# SCH_carw_2026-01-21.net
KiCad netlist of a schematic drawn in EasyEDA
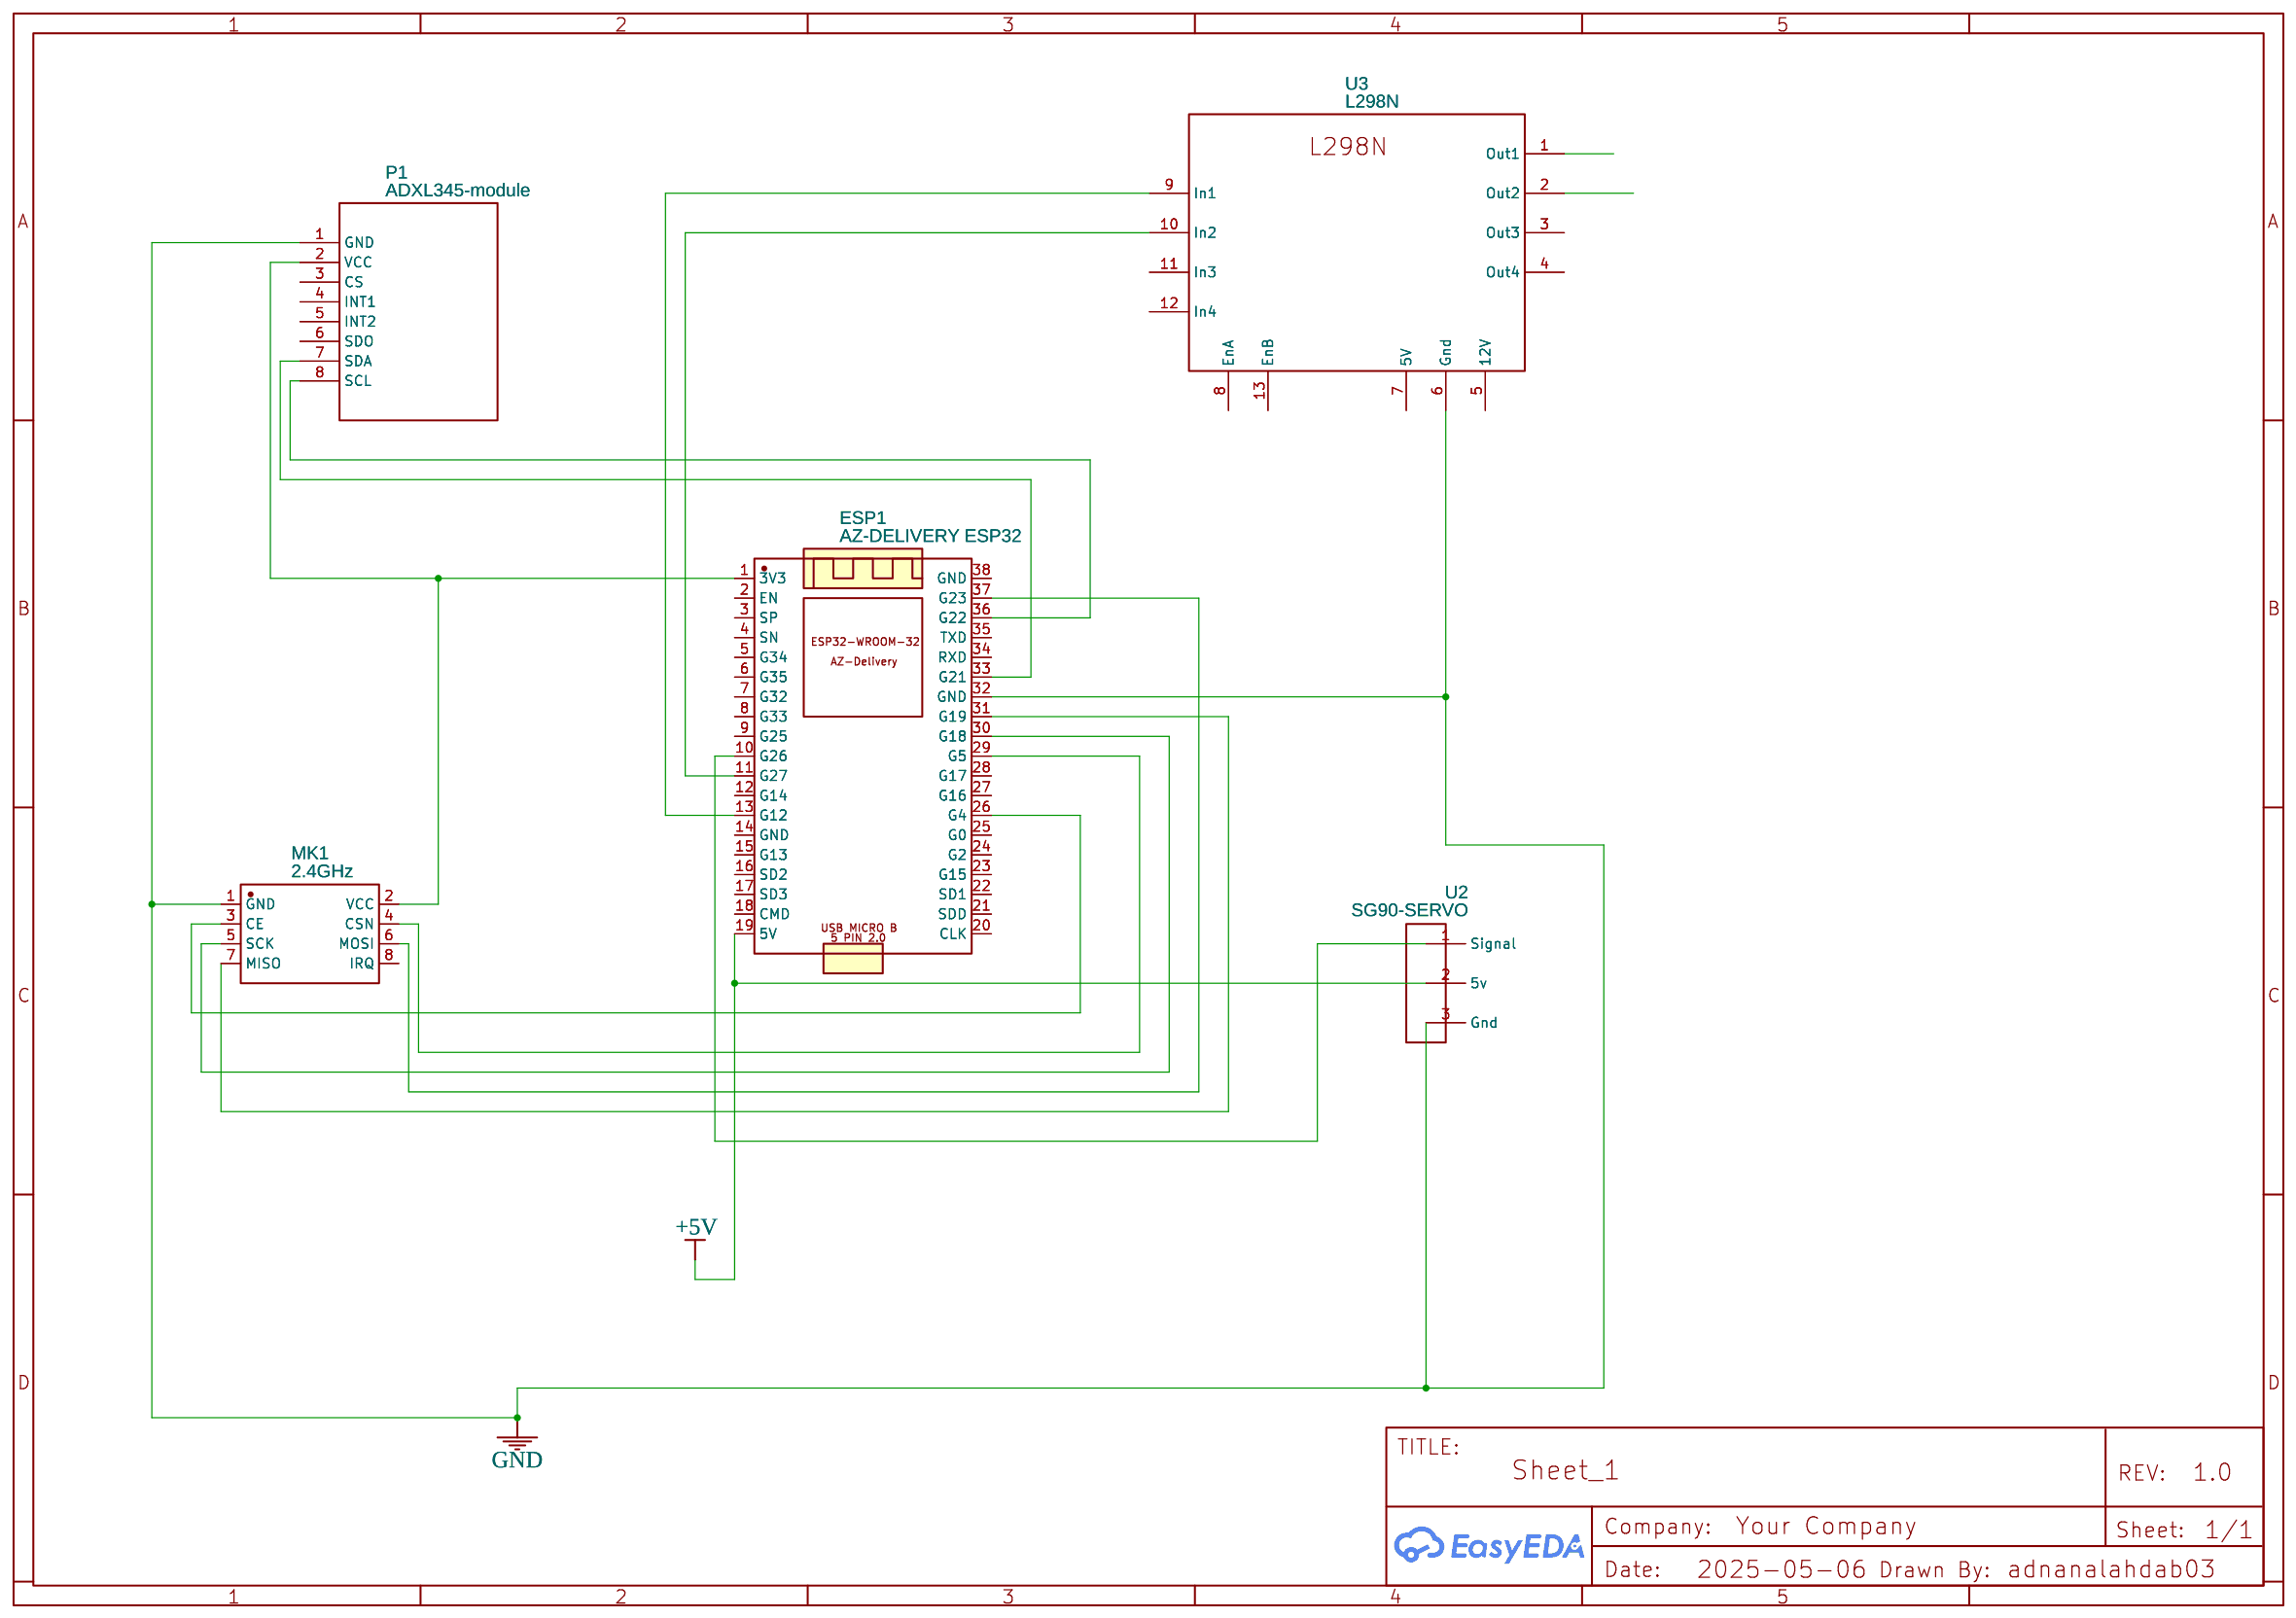
[diagram p0: schematic sheet]

(export (version "E")
  (design (tool "Eeschema 10.0.6"))
  (components
    (comp (ref "ESP1")
      (value "AZ-DELIVERY ESP32")
      (fields (field (name "Manufacturer") "AZ-DELIVERY"))
      (libsource (lib "") (part "AZ-DELIVERY ESP32"))
    )
    (comp (ref "MK1")
      (value "2.4GHz")
      (fields (field (name "Manufacturer Part") "NF-04") (field (name "Manufacturer") "Ai-Thinker(安信可)"))
      (libsource (lib "") (part "NRF24L01"))
    )
    (comp (ref "P1") (value "ADXL345-module") (libsource (lib "") (part "ADXL345-module")))
    (comp (ref "U2") (value "SG90-SERVO") (libsource (lib "") (part "SG90-SERVO")))
    (comp (ref "U3") (value "L298N") (libsource (lib "") (part "L298N")))
  )
  (nets
    (net (code "1") (name "+5V") (class "Default")
      (node (ref "ESP1") (pin "19") (pinfunction "5V_19") (pintype "passive"))
      (node (ref "U2") (pin "2") (pinfunction "5v_2") (pintype "unspecified"))
    )
    (net (code "2") (name "GND") (class "Default")
      (node (ref "ESP1") (pin "32") (pinfunction "GND_32") (pintype "unspecified"))
      (node (ref "MK1") (pin "1") (pinfunction "GND_1") (pintype "unspecified"))
      (node (ref "P1") (pin "1") (pinfunction "GND_1") (pintype "unspecified"))
      (node (ref "U2") (pin "3") (pinfunction "Gnd_3") (pintype "unspecified"))
      (node (ref "U3") (pin "6") (pinfunction "Gnd_6") (pintype "unspecified"))
    )
    (net (code "3") (name "Net-(ESP1-3V3)") (class "Default")
      (node (ref "ESP1") (pin "1") (pinfunction "3V3_1") (pintype "passive"))
      (node (ref "MK1") (pin "2") (pinfunction "VCC_2") (pintype "unspecified"))
      (node (ref "P1") (pin "2") (pinfunction "VCC_2") (pintype "unspecified"))
    )
    (net (code "4") (name "Net-(ESP1-G4)") (class "Default")
      (node (ref "ESP1") (pin "26") (pinfunction "G4_26") (pintype "unspecified"))
      (node (ref "MK1") (pin "3") (pinfunction "CE_3") (pintype "unspecified"))
    )
    (net (code "5") (name "Net-(ESP1-G5)") (class "Default")
      (node (ref "ESP1") (pin "29") (pinfunction "G5_29") (pintype "unspecified"))
      (node (ref "MK1") (pin "4") (pinfunction "CSN_4") (pintype "unspecified"))
    )
    (net (code "6") (name "Net-(ESP1-G12)") (class "Default")
      (node (ref "ESP1") (pin "13") (pinfunction "G12_13") (pintype "unspecified"))
      (node (ref "U3") (pin "9") (pinfunction "In1_9") (pintype "unspecified"))
    )
    (net (code "7") (name "Net-(ESP1-G18)") (class "Default")
      (node (ref "ESP1") (pin "30") (pinfunction "G18_30") (pintype "unspecified"))
      (node (ref "MK1") (pin "5") (pinfunction "SCK_5") (pintype "unspecified"))
    )
    (net (code "8") (name "Net-(ESP1-G19)") (class "Default")
      (node (ref "ESP1") (pin "31") (pinfunction "G19_31") (pintype "unspecified"))
      (node (ref "MK1") (pin "7") (pinfunction "MISO_7") (pintype "unspecified"))
    )
    (net (code "9") (name "Net-(ESP1-G21)") (class "Default")
      (node (ref "ESP1") (pin "33") (pinfunction "G21_33") (pintype "unspecified"))
      (node (ref "P1") (pin "7") (pinfunction "SDA_7") (pintype "unspecified"))
    )
    (net (code "10") (name "Net-(ESP1-G22)") (class "Default")
      (node (ref "ESP1") (pin "36") (pinfunction "G22_36") (pintype "unspecified"))
      (node (ref "P1") (pin "8") (pinfunction "SCL_8") (pintype "unspecified"))
    )
    (net (code "11") (name "Net-(ESP1-G23)") (class "Default")
      (node (ref "ESP1") (pin "37") (pinfunction "G23_37") (pintype "unspecified"))
      (node (ref "MK1") (pin "6") (pinfunction "MOSI_6") (pintype "unspecified"))
    )
    (net (code "12") (name "Net-(ESP1-G26)") (class "Default")
      (node (ref "ESP1") (pin "10") (pinfunction "G26_10") (pintype "unspecified"))
      (node (ref "U2") (pin "1") (pinfunction "Signal_1") (pintype "unspecified"))
    )
    (net (code "13") (name "Net-(ESP1-G27)") (class "Default")
      (node (ref "ESP1") (pin "11") (pinfunction "G27_11") (pintype "unspecified"))
      (node (ref "U3") (pin "10") (pinfunction "In2_10") (pintype "unspecified"))
    )
    (net (code "14") (name "unconnected-(ESP1-CLK-Pad20)") (class "Default")
      (node (ref "ESP1") (pin "20") (pinfunction "CLK_20") (pintype "unspecified"))
    )
    (net (code "15") (name "unconnected-(ESP1-CMD-Pad18)") (class "Default")
      (node (ref "ESP1") (pin "18") (pinfunction "CMD_18") (pintype "unspecified"))
    )
    (net (code "16") (name "unconnected-(ESP1-EN-Pad2)") (class "Default")
      (node (ref "ESP1") (pin "2") (pinfunction "EN_2") (pintype "unspecified"))
    )
    (net (code "17") (name "unconnected-(ESP1-G0-Pad25)") (class "Default")
      (node (ref "ESP1") (pin "25") (pinfunction "G0_25") (pintype "unspecified"))
    )
    (net (code "18") (name "unconnected-(ESP1-G2-Pad24)") (class "Default")
      (node (ref "ESP1") (pin "24") (pinfunction "G2_24") (pintype "unspecified"))
    )
    (net (code "19") (name "unconnected-(ESP1-G13-Pad15)") (class "Default")
      (node (ref "ESP1") (pin "15") (pinfunction "G13_15") (pintype "unspecified"))
    )
    (net (code "20") (name "unconnected-(ESP1-G14-Pad12)") (class "Default")
      (node (ref "ESP1") (pin "12") (pinfunction "G14_12") (pintype "unspecified"))
    )
    (net (code "21") (name "unconnected-(ESP1-G15-Pad23)") (class "Default")
      (node (ref "ESP1") (pin "23") (pinfunction "G15_23") (pintype "unspecified"))
    )
    (net (code "22") (name "unconnected-(ESP1-G16-Pad27)") (class "Default")
      (node (ref "ESP1") (pin "27") (pinfunction "G16_27") (pintype "unspecified"))
    )
    (net (code "23") (name "unconnected-(ESP1-G17-Pad28)") (class "Default")
      (node (ref "ESP1") (pin "28") (pinfunction "G17_28") (pintype "unspecified"))
    )
    (net (code "24") (name "unconnected-(ESP1-G25-Pad9)") (class "Default")
      (node (ref "ESP1") (pin "9") (pinfunction "G25_9") (pintype "unspecified"))
    )
    (net (code "25") (name "unconnected-(ESP1-G32-Pad7)") (class "Default")
      (node (ref "ESP1") (pin "7") (pinfunction "G32_7") (pintype "unspecified"))
    )
    (net (code "26") (name "unconnected-(ESP1-G33-Pad8)") (class "Default")
      (node (ref "ESP1") (pin "8") (pinfunction "G33_8") (pintype "unspecified"))
    )
    (net (code "27") (name "unconnected-(ESP1-G34-Pad5)") (class "Default")
      (node (ref "ESP1") (pin "5") (pinfunction "G34_5") (pintype "unspecified"))
    )
    (net (code "28") (name "unconnected-(ESP1-G35-Pad6)") (class "Default")
      (node (ref "ESP1") (pin "6") (pinfunction "G35_6") (pintype "unspecified"))
    )
    (net (code "29") (name "unconnected-(ESP1-GND-Pad14)") (class "Default")
      (node (ref "ESP1") (pin "14") (pinfunction "GND_14") (pintype "unspecified"))
    )
    (net (code "30") (name "unconnected-(ESP1-GND-Pad38)") (class "Default")
      (node (ref "ESP1") (pin "38") (pinfunction "GND_38") (pintype "unspecified"))
    )
    (net (code "31") (name "unconnected-(ESP1-RXD-Pad34)") (class "Default")
      (node (ref "ESP1") (pin "34") (pinfunction "RXD_34") (pintype "unspecified"))
    )
    (net (code "32") (name "unconnected-(ESP1-SD1-Pad22)") (class "Default")
      (node (ref "ESP1") (pin "22") (pinfunction "SD1_22") (pintype "unspecified"))
    )
    (net (code "33") (name "unconnected-(ESP1-SD2-Pad16)") (class "Default")
      (node (ref "ESP1") (pin "16") (pinfunction "SD2_16") (pintype "unspecified"))
    )
    (net (code "34") (name "unconnected-(ESP1-SD3-Pad17)") (class "Default")
      (node (ref "ESP1") (pin "17") (pinfunction "SD3_17") (pintype "unspecified"))
    )
    (net (code "35") (name "unconnected-(ESP1-SDD-Pad21)") (class "Default")
      (node (ref "ESP1") (pin "21") (pinfunction "SDD_21") (pintype "unspecified"))
    )
    (net (code "36") (name "unconnected-(ESP1-SN-Pad4)") (class "Default")
      (node (ref "ESP1") (pin "4") (pinfunction "SN_4") (pintype "unspecified"))
    )
    (net (code "37") (name "unconnected-(ESP1-SP-Pad3)") (class "Default")
      (node (ref "ESP1") (pin "3") (pinfunction "SP_3") (pintype "unspecified"))
    )
    (net (code "38") (name "unconnected-(ESP1-TXD-Pad35)") (class "Default")
      (node (ref "ESP1") (pin "35") (pinfunction "TXD_35") (pintype "unspecified"))
    )
    (net (code "39") (name "unconnected-(MK1-IRQ-Pad8)") (class "Default")
      (node (ref "MK1") (pin "8") (pinfunction "IRQ_8") (pintype "unspecified"))
    )
    (net (code "40") (name "unconnected-(P1-CS-Pad3)") (class "Default")
      (node (ref "P1") (pin "3") (pinfunction "CS_3") (pintype "unspecified"))
    )
    (net (code "41") (name "unconnected-(P1-INT1-Pad4)") (class "Default")
      (node (ref "P1") (pin "4") (pinfunction "INT1_4") (pintype "unspecified"))
    )
    (net (code "42") (name "unconnected-(P1-INT2-Pad5)") (class "Default")
      (node (ref "P1") (pin "5") (pinfunction "INT2_5") (pintype "unspecified"))
    )
    (net (code "43") (name "unconnected-(P1-SDO-Pad6)") (class "Default")
      (node (ref "P1") (pin "6") (pinfunction "SDO_6") (pintype "unspecified"))
    )
    (net (code "44") (name "unconnected-(U3-5V-Pad7)") (class "Default")
      (node (ref "U3") (pin "7") (pinfunction "5V_7") (pintype "unspecified"))
    )
    (net (code "45") (name "unconnected-(U3-12V-Pad5)") (class "Default")
      (node (ref "U3") (pin "5") (pinfunction "12V_5") (pintype "unspecified"))
    )
    (net (code "46") (name "unconnected-(U3-EnA-Pad8)") (class "Default")
      (node (ref "U3") (pin "8") (pinfunction "EnA_8") (pintype "unspecified"))
    )
    (net (code "47") (name "unconnected-(U3-EnB-Pad13)") (class "Default")
      (node (ref "U3") (pin "13") (pinfunction "EnB_13") (pintype "unspecified"))
    )
    (net (code "48") (name "unconnected-(U3-In3-Pad11)") (class "Default")
      (node (ref "U3") (pin "11") (pinfunction "In3_11") (pintype "unspecified"))
    )
    (net (code "49") (name "unconnected-(U3-In4-Pad12)") (class "Default")
      (node (ref "U3") (pin "12") (pinfunction "In4_12") (pintype "unspecified"))
    )
    (net (code "50") (name "unconnected-(U3-Out1-Pad1)") (class "Default")
      (node (ref "U3") (pin "1") (pinfunction "Out1_1") (pintype "unspecified"))
    )
    (net (code "51") (name "unconnected-(U3-Out2-Pad2)") (class "Default")
      (node (ref "U3") (pin "2") (pinfunction "Out2_2") (pintype "unspecified"))
    )
    (net (code "52") (name "unconnected-(U3-Out3-Pad3)") (class "Default")
      (node (ref "U3") (pin "3") (pinfunction "Out3_3") (pintype "unspecified"))
    )
    (net (code "53") (name "unconnected-(U3-Out4-Pad4)") (class "Default")
      (node (ref "U3") (pin "4") (pinfunction "Out4_4") (pintype "unspecified"))
    )
  )
)
